# Power.net
KiCad netlist of a schematic drawn in Altium Designer
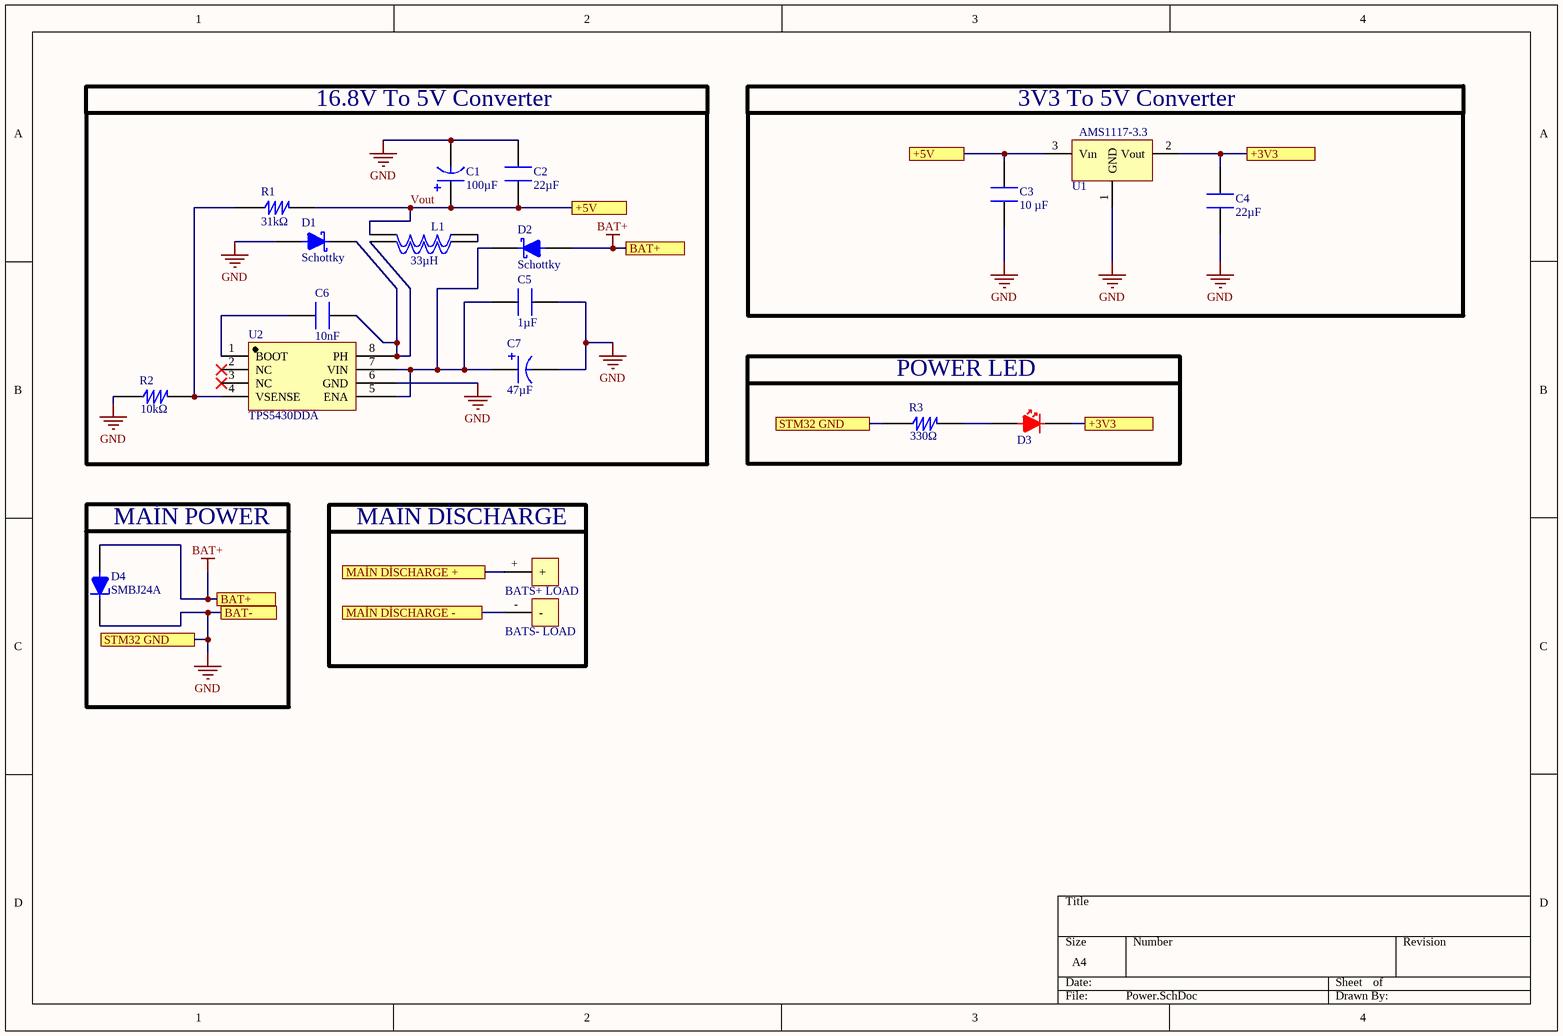
[diagram p0: Power.SchDoc]

(export (version "E")
  (design (tool "Eeschema 10.0.6"))
  (components
    (comp (ref "BATS+ LOAD")
      (value "BATTERY + 1S")
      (footprint "BATTERY +1S")
      (description "battery + pad")
      (libsource (lib "Ahaltech BMS") (part "BATTERY + 1S"))
    )
    (comp (ref "BATS- LOAD")
      (value "BATTERY -1S")
      (footprint "BATTERY -1S")
      (description "battery - pad")
      (libsource (lib "Ahaltech BMS") (part "BATTERY -1S"))
    )
    (comp (ref "C1")
      (value "100µF")
      (footprint "CAP_EEE-1AA101WR")
      (description "CAP ALUM 100UF 20% 10V SMD")
      (fields
        (field (name "MANUFACTURER") "Panasonic")
        (field (name "MANUFACTURER PART NUMBER") "EEE-1AA101WR")
      )
      (libsource (lib "Ahaltech BMS") (part "CAP ALUM 100UF 10V"))
    )
    (comp (ref "C2")
      (value "22µF")
      (footprint "CAP CER 1210")
      (description "CAP CER 22UF 10V X7R 1210")
      (fields
        (field (name "MANUFACTURER") "KEMET")
        (field (name "MANUFACTURER PART NUMBER") "C1210C226J8RACTU")
      )
      (libsource (lib "Ahaltech BMS") (part "CAP CER 22UF 10V 1210"))
    )
    (comp (ref "C3")
      (value "0805W106K500CC")
      (footprint "CAP CER 0805")
      (description "10 µF ±10% 50V Ceramic Capacitor X5R 0805 (2012 Metric)")
      (fields (field (name "TOLERANCE") "±10%") (field (name "CAPACITANCE") "10 µF"))
      (libsource (lib "Ahaltech BMS") (part "CAP CER 10UF 50V 0805"))
    )
    (comp (ref "C4")
      (value "22µF")
      (footprint "CAP CER 1210")
      (description "CAP CER 22UF 10V X7R 1210")
      (fields
        (field (name "MANUFACTURER") "KEMET")
        (field (name "MANUFACTURER PART NUMBER") "C1210C226J8RACTU")
      )
      (libsource (lib "") (part "CAP CER 22UF 10V 1210_1"))
    )
    (comp (ref "C5")
      (value "1µF")
      (footprint "CAP CER 0805")
      (description "CAP CER 1UF 50V X7R 0805")
      (fields
        (field (name "MANUFACTURER") "Samsung Electro-Mechanics")
        (field (name "MANUFACTURER PART NUMBER") "CL21B105KBFNNNE")
      )
      (libsource (lib "Ahaltech BMS") (part "CAP CER 1UF 50V 0805"))
    )
    (comp (ref "C6")
      (value "10nF")
      (footprint "CAP CER 0603")
      (description "CAP CER 10000PF 50V X7R 0603")
      (fields
        (field (name "MANUFACTURER") "KEMET")
        (field (name "MANUFACTURER PART NUMBER") "C0603C103J5RACTU")
      )
      (libsource (lib "Ahaltech BMS") (part "CAP CER 0.01µF (10 nF) 50V 0603"))
    )
    (comp (ref "C7")
      (value "47µF")
      (footprint "CAP_EEE-FK1E470P")
      (description "Radial Can - SMD ALUMINUM ELECTROLYTIC CAPACITOR FK 25V 47muF ±20% 0.248Dia 6.30mm")
      (fields
        (field (name "MANUFACTURER") "Panasonic")
        (field (name "MANUFACTURER PART NUMBER") "EEEFK1E470P")
      )
      (libsource (lib "Ahaltech BMS") (part "CAP ALUM 47UF 25V"))
    )
    (comp (ref "D1")
      (value "SS54")
      (footprint "DO-214AC (SMA)")
      (description "Diode Schottky 40 V 5A Surface Mount SMA")
      (fields (field (name "TECHNOLOGY") "Schottky"))
      (libsource (lib "Ahaltech BMS") (part "DIODE SCHOTTKY 40V 5A"))
    )
    (comp (ref "D2")
      (value "SS54")
      (footprint "DO-214AC (SMA)")
      (description "Diode Schottky 40 V 5A Surface Mount SMA")
      (fields (field (name "TECHNOLOGY") "Schottky"))
      (libsource (lib "Ahaltech BMS") (part "DIODE SCHOTTKY 40V 5A"))
    )
    (comp (ref "D3")
      (value "LTST-C190KRKT")
      (footprint "LED 0603")
      (description "Red 631nm LED Indication - Discrete 2V 0603 (1608 Metric)")
      (fields (field (name "MANUFACTURER") "Lite-On") (field (name "TOLERANCE") "20%"))
      (libsource (lib "Ahaltech BMS") (part "LED RED CLEAR"))
    )
    (comp (ref "D4")
      (value "SMBJ24A")
      (footprint "SMBJ24A")
      (description "TVS Diode, SMBJ, Unidirectional, 24 V, 38.9 V, DO-214AA (SMB), 2 Pins")
      (fields (field (name "MANUFACTURER") "Bourns") (field (name "MANUFACTURER PART NUMBER") "SMBJ24A"))
      (libsource (lib "Ahaltech BMS") (part "DIODE TVS 40VC"))
    )
    (comp (ref "L1")
      (value "33µH")
      (footprint "SRF0703 Series INDUCTOR")
      (description "INDUCT ARRAY 2 COIL 33UH SMD")
      (fields (field (name "MANUFACTURER") "Bourns") (field (name "MANUFACTURER PART NUMBER") "SRF0703-330M"))
      (libsource (lib "Ahaltech BMS") (part "INDUCTOR 33UH"))
    )
    (comp (ref "R1")
      (value "31kΩ")
      (footprint "RES 2010")
      (description "31 kOhms ±0.01% 0.5W, 1/2W Chip Resistor 2010 (5025 Metric) Non-Inductive Metal Foil")
      (fields
        (field (name "MANUFACTURER") "Vishay")
        (field (name "MANUFACTURER PART NUMBER") "Y162731K0000T9R")
      )
      (libsource (lib "Ahaltech BMS") (part "RES 31K OHM 1/2W 2010"))
    )
    (comp (ref "R2")
      (value "10kΩ")
      (footprint "RES 0603")
      (description "RES 10K OHM 1% 1/10W 0603")
      (fields
        (field (name "MANUFACTURER") "Stackpole Electronics")
        (field (name "MANUFACTURER PART NUMBER") "RMCF0603FT10K0")
      )
      (libsource (lib "Ahaltech BMS") (part "RES 10K OHM 1/10W 0603"))
    )
    (comp (ref "R3")
      (value "330Ω")
      (footprint "RES 0603")
      (description "330 Ohms ±1% 0.1W, 1/10W Chip Resistor 0603 (1608 Metric) Thick Film")
      (fields
        (field (name "MANUFACTURER") "TE Connectivity")
        (field (name "MANUFACTURER PART NUMBER") "1622918-1")
      )
      (libsource (lib "Ahaltech BMS") (part "RES 330 OHM 1/10W 0603"))
    )
    (comp (ref "U1")
      (value "AMS1117-3.3")
      (footprint "SOT-223-3L")
      (description "IC REG LINEAR 3.3V 1A SOT-223-3L")
      (fields (field (name "MANUFACTURER") "ams") (field (name "MANUFACTURER PART NUMBER") "AMS1117-3.3"))
      (libsource (lib "Ahaltech BMS") (part "AMS1117-3.3"))
    )
    (comp (ref "U2")
      (value "TPS5430DDA")
      (footprint "8SOPWR")
      (description "5.5V to 36V Input, 3A, 500kHz Step-Down Converter 8-SO PowerPAD 0 to 0")
      (fields
        (field (name "MANUFACTURER") "Texas Instruments")
        (field (name "SUPPLIER PART NUMBER") "TPS5430DDA")
      )
      (libsource (lib "Ahaltech BMS") (part "TPS5430DDA"))
    )
  )
  (nets
    (net (code "1") (name "/+3V3") (class "Default")
      (node (ref "C4") (pin "1") (pinfunction "1_1") (pintype "passive"))
      (node (ref "D3") (pin "2") (pinfunction "2_2") (pintype "passive"))
      (node (ref "U1") (pin "2") (pinfunction "Vout_2") (pintype "passive"))
    )
    (net (code "2") (name "/MAİN DİSCHARGE +") (class "Default")
      (node (ref "BATS+ LOAD") (pin "+") (pinfunction "+_+") (pintype "passive"))
    )
    (net (code "3") (name "/MAİN DİSCHARGE -") (class "Default")
      (node (ref "BATS- LOAD") (pin "-") (pinfunction "-_-") (pintype "passive"))
    )
    (net (code "4") (name "/Vout") (class "Default")
      (node (ref "C1") (pin "1") (pinfunction "1_1") (pintype "passive"))
      (node (ref "C2") (pin "1") (pinfunction "1_1") (pintype "passive"))
      (node (ref "C3") (pin "1") (pinfunction "1_1") (pintype "passive"))
      (node (ref "L1") (pin "1") (pinfunction "1_1") (pintype "passive"))
      (node (ref "R1") (pin "2") (pinfunction "2_2") (pintype "passive"))
      (node (ref "U1") (pin "3") (pinfunction "Vın_3") (pintype "passive"))
    )
    (net (code "5") (name "BAT+") (class "Default")
      (node (ref "D2") (pin "1") (pinfunction "1_1") (pintype "passive"))
      (node (ref "D4") (pin "1") (pinfunction "1_1") (pintype "passive"))
    )
    (net (code "6") (name "GND") (class "Default")
      (node (ref "C1") (pin "2") (pinfunction "2_2") (pintype "passive"))
      (node (ref "C2") (pin "2") (pinfunction "2_2") (pintype "passive"))
      (node (ref "C3") (pin "2") (pinfunction "2_2") (pintype "passive"))
      (node (ref "C4") (pin "2") (pinfunction "2_2") (pintype "passive"))
      (node (ref "C5") (pin "2") (pinfunction "2_2") (pintype "passive"))
      (node (ref "C7") (pin "2") (pinfunction "2_2") (pintype "passive"))
      (node (ref "D1") (pin "1") (pinfunction "1_1") (pintype "passive"))
      (node (ref "D4") (pin "2") (pinfunction "2_2") (pintype "passive"))
      (node (ref "R2") (pin "1") (pinfunction "1_1") (pintype "passive"))
      (node (ref "R3") (pin "1") (pinfunction "1_1") (pintype "passive"))
      (node (ref "U1") (pin "1") (pinfunction "GND_1") (pintype "passive"))
      (node (ref "U2") (pin "6") (pinfunction "GND_6") (pintype "passive"))
    )
    (net (code "7") (name "Net-(D3-Pad1)") (class "Default")
      (node (ref "D3") (pin "1") (pinfunction "1_1") (pintype "passive"))
      (node (ref "R3") (pin "2") (pinfunction "2_2") (pintype "passive"))
    )
    (net (code "8") (name "Net-(L1-Pad3)") (class "Default")
      (node (ref "L1") (pin "3") (pinfunction "3_3") (pintype "passive"))
    )
    (net (code "9") (name "Net-(U2-BOOT)") (class "Default")
      (node (ref "C6") (pin "2") (pinfunction "2_2") (pintype "passive"))
      (node (ref "U2") (pin "1") (pinfunction "BOOT_1") (pintype "passive"))
    )
    (net (code "10") (name "Net-(U2-ENA)") (class "Default")
      (node (ref "C5") (pin "1") (pinfunction "1_1") (pintype "passive"))
      (node (ref "C7") (pin "1") (pinfunction "1_1") (pintype "passive"))
      (node (ref "D2") (pin "2") (pinfunction "2_2") (pintype "passive"))
      (node (ref "U2") (pin "5") (pinfunction "ENA_5") (pintype "passive"))
      (node (ref "U2") (pin "7") (pinfunction "VIN_7") (pintype "passive"))
    )
    (net (code "11") (name "Net-(U2-PH)") (class "Default")
      (node (ref "C6") (pin "1") (pinfunction "1_1") (pintype "passive"))
      (node (ref "D1") (pin "2") (pinfunction "2_2") (pintype "passive"))
      (node (ref "L1") (pin "2") (pinfunction "2_2") (pintype "passive"))
      (node (ref "U2") (pin "8") (pinfunction "PH_8") (pintype "passive"))
    )
    (net (code "12") (name "Net-(U2-VSENSE)") (class "Default")
      (node (ref "R1") (pin "1") (pinfunction "1_1") (pintype "passive"))
      (node (ref "R2") (pin "2") (pinfunction "2_2") (pintype "passive"))
      (node (ref "U2") (pin "4") (pinfunction "VSENSE_4") (pintype "passive"))
    )
    (net (code "13") (name "unconnected-(U2-NC-Pad2)") (class "Default")
      (node (ref "U2") (pin "2") (pinfunction "NC_2") (pintype "passive+no_connect"))
    )
    (net (code "14") (name "unconnected-(U2-NC-Pad3)") (class "Default")
      (node (ref "U2") (pin "3") (pinfunction "NC_3") (pintype "passive+no_connect"))
    )
  )
)
